# UCS.net
KiCad netlist of a schematic drawn in EAGLE
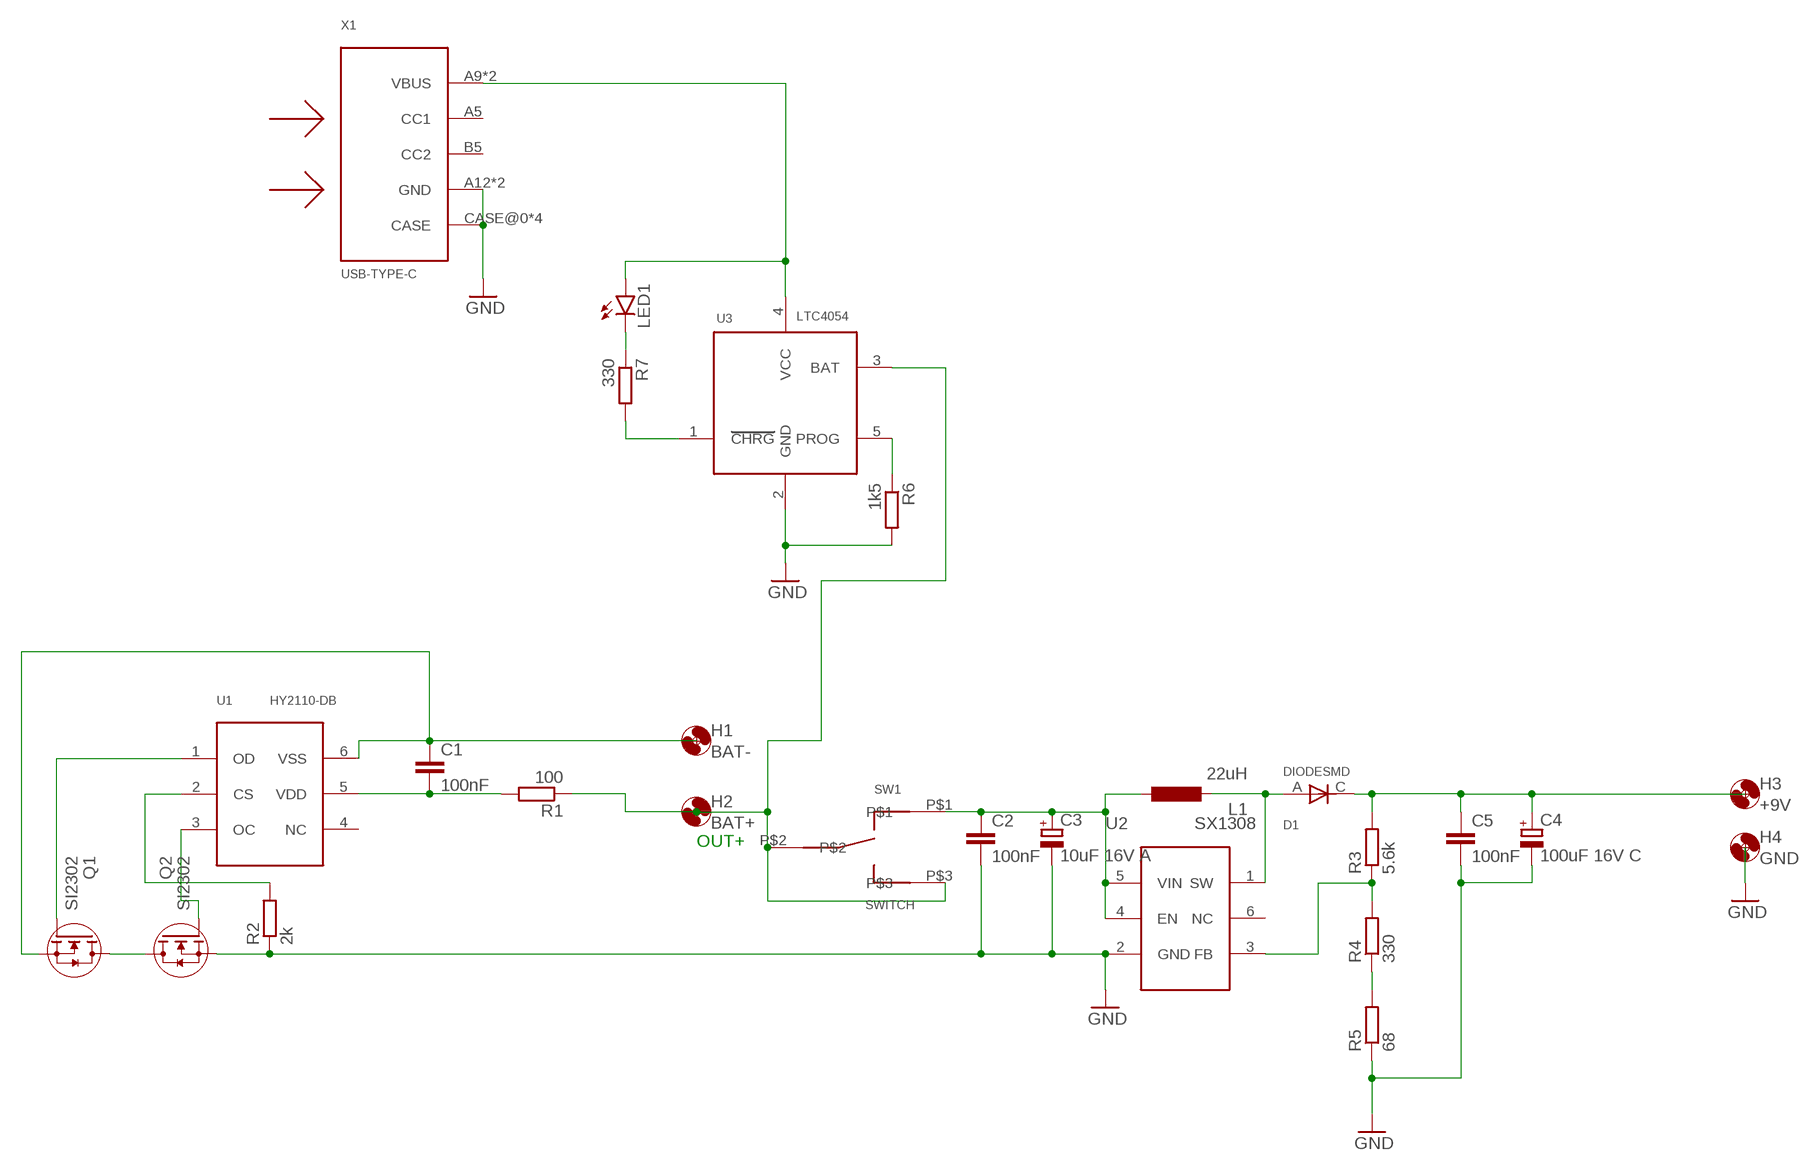
[diagram p0: schematic, sheet 1]

(export (version "E")
  (design (tool "Eeschema 10.0.6"))
  (components
    (comp (ref "C1")
      (value "100nF")
      (footprint "eagle-import:C0805")
      (libsource (lib "eagle-import") (part "C-EUC0805"))
    )
    (comp (ref "C2")
      (value "100nF")
      (footprint "eagle-import:C0805")
      (libsource (lib "eagle-import") (part "C-EUC0805"))
    )
    (comp (ref "C3")
      (value "10uF 16V A")
      (footprint "eagle-import:SMC_A")
      (libsource (lib "eagle-import") (part "CPOL-EUSMCA"))
    )
    (comp (ref "C4")
      (value "100uF 16V C")
      (footprint "eagle-import:SMC_C")
      (libsource (lib "eagle-import") (part "CPOL-EUSMCC"))
    )
    (comp (ref "C5")
      (value "100nF")
      (footprint "eagle-import:C0805")
      (libsource (lib "eagle-import") (part "C-EUC0805"))
    )
    (comp (ref "D1")
      (value "DIODESMD")
      (footprint "eagle-import:DO214AC")
      (libsource (lib "eagle-import") (part "DIODESMD"))
    )
    (comp (ref "H1")
      (value "BAT-")
      (footprint "eagle-import:3,0")
      (libsource (lib "eagle-import") (part "MOUNT-HOLE3.0"))
    )
    (comp (ref "H2")
      (value "BAT+")
      (footprint "eagle-import:3,0")
      (libsource (lib "eagle-import") (part "MOUNT-HOLE3.0"))
    )
    (comp (ref "H3")
      (value "+9V")
      (footprint "eagle-import:3,0")
      (libsource (lib "eagle-import") (part "MOUNT-HOLE3.0"))
    )
    (comp (ref "H4")
      (value "GND")
      (footprint "eagle-import:3,0")
      (libsource (lib "eagle-import") (part "MOUNT-HOLE3.0"))
    )
    (comp (ref "L1")
      (value "22uH")
      (footprint "eagle-import:L7_7_5")
      (libsource (lib "eagle-import") (part "L-SMD-775"))
    )
    (comp (ref "LED1")
      (value "LEDCHIPLED_0603")
      (footprint "eagle-import:CHIPLED_0603")
      (libsource (lib "eagle-import") (part "LEDCHIPLED_0603"))
    )
    (comp (ref "Q1")
      (value "SI2302")
      (footprint "eagle-import:SOT-23-GSD")
      (libsource (lib "eagle-import") (part "SI2302"))
    )
    (comp (ref "Q2")
      (value "SI2302")
      (footprint "eagle-import:SOT-23-GSD")
      (libsource (lib "eagle-import") (part "SI2302"))
    )
    (comp (ref "R1")
      (value "100")
      (footprint "eagle-import:R0805")
      (libsource (lib "eagle-import") (part "R-EU_R0805"))
    )
    (comp (ref "R2")
      (value "2k")
      (footprint "eagle-import:R0805")
      (libsource (lib "eagle-import") (part "R-EU_R0805"))
    )
    (comp (ref "R3")
      (value "5.6k")
      (footprint "eagle-import:R0805")
      (libsource (lib "eagle-import") (part "R-EU_R0805"))
    )
    (comp (ref "R4")
      (value "330")
      (footprint "eagle-import:R0805")
      (libsource (lib "eagle-import") (part "R-EU_R0805"))
    )
    (comp (ref "R5")
      (value "68")
      (footprint "eagle-import:R0805")
      (libsource (lib "eagle-import") (part "R-EU_R0805"))
    )
    (comp (ref "R6")
      (value "1k5")
      (footprint "eagle-import:R0805")
      (libsource (lib "eagle-import") (part "R-EU_R0805"))
    )
    (comp (ref "R7")
      (value "330")
      (footprint "eagle-import:R0805")
      (libsource (lib "eagle-import") (part "R-EU_R0805"))
    )
    (comp (ref "SW1")
      (value "SWITCH")
      (footprint "eagle-import:SWITCH")
      (libsource (lib "eagle-import") (part "SWITCH"))
    )
    (comp (ref "U1")
      (value "HY2110-DB")
      (footprint "eagle-import:SOT-23-6")
      (libsource (lib "eagle-import") (part "HY2110-DB"))
    )
    (comp (ref "U2")
      (value "SX1308")
      (footprint "eagle-import:SOT-23-6")
      (libsource (lib "eagle-import") (part "SX1308"))
    )
    (comp (ref "U3")
      (value "LTC4054")
      (footprint "eagle-import:SOT-23-5")
      (libsource (lib "eagle-import") (part "LTC4054"))
    )
    (comp (ref "X1")
      (value "USB-TYPE-C")
      (footprint "eagle-import:USB-TYPE-C")
      (libsource (lib "eagle-import") (part "USB-TYPE-C"))
    )
  )
  (nets
    (net (code "1") (name "GND") (class "Default")
      (node (ref "C2") (pin "2") (pinfunction "2_2") (pintype "passive"))
      (node (ref "C3") (pin "-") (pinfunction "-_-") (pintype "passive"))
      (node (ref "C4") (pin "-") (pinfunction "-_-") (pintype "passive"))
      (node (ref "C5") (pin "2") (pinfunction "2_2") (pintype "passive"))
      (node (ref "H4") (pin "P$1") (pinfunction "P$1_P$1") (pintype "bidirectional"))
      (node (ref "Q2") (pin "S") (pinfunction "S_S") (pintype "passive"))
      (node (ref "R2") (pin "1") (pinfunction "1_1") (pintype "passive"))
      (node (ref "R5") (pin "1") (pinfunction "1_1") (pintype "passive"))
      (node (ref "R6") (pin "2") (pinfunction "2_2") (pintype "passive"))
      (node (ref "U2") (pin "2") (pinfunction "GND_2") (pintype "bidirectional"))
      (node (ref "U3") (pin "2") (pinfunction "GND_2") (pintype "bidirectional"))
      (node (ref "X1") (pin "A12") (pinfunction "GND_A12") (pintype "bidirectional"))
      (node (ref "X1") (pin "B12") (pinfunction "GND_B12") (pintype "bidirectional"))
      (node (ref "X1") (pin "CASE@0") (pinfunction "CASE_CASE@0") (pintype "bidirectional"))
      (node (ref "X1") (pin "CASE@1") (pinfunction "CASE_CASE@1") (pintype "bidirectional"))
      (node (ref "X1") (pin "CASE@2") (pinfunction "CASE_CASE@2") (pintype "bidirectional"))
      (node (ref "X1") (pin "CASE@3") (pinfunction "CASE_CASE@3") (pintype "bidirectional"))
    )
    (net (code "2") (name "Net-(D1-ANOD)") (class "Default")
      (node (ref "D1") (pin "A") (pinfunction "ANOD_A") (pintype "power_in"))
      (node (ref "L1") (pin "P$2") (pinfunction "2_P$2") (pintype "passive"))
      (node (ref "U2") (pin "1") (pinfunction "SW_1") (pintype "bidirectional"))
    )
    (net (code "3") (name "Net-(D1-KATOD)") (class "Default")
      (node (ref "C4") (pin "+") (pinfunction "+_+") (pintype "passive"))
      (node (ref "C5") (pin "1") (pinfunction "1_1") (pintype "passive"))
      (node (ref "D1") (pin "C") (pinfunction "KATOD_C") (pintype "power_in"))
      (node (ref "H3") (pin "P$1") (pinfunction "P$1_P$1") (pintype "bidirectional"))
      (node (ref "R3") (pin "2") (pinfunction "2_2") (pintype "passive"))
    )
    (net (code "4") (name "Net-(L1-1)") (class "Default")
      (node (ref "C2") (pin "1") (pinfunction "1_1") (pintype "passive"))
      (node (ref "C3") (pin "+") (pinfunction "+_+") (pintype "passive"))
      (node (ref "L1") (pin "P$1") (pinfunction "1_P$1") (pintype "passive"))
      (node (ref "SW1") (pin "P$1") (pinfunction "P$1_P$1") (pintype "bidirectional"))
      (node (ref "U2") (pin "4") (pinfunction "EN_4") (pintype "bidirectional"))
      (node (ref "U2") (pin "5") (pinfunction "VIN_5") (pintype "bidirectional"))
    )
    (net (code "5") (name "Net-(LED1-PadC)") (class "Default")
      (node (ref "LED1") (pin "C") (pinfunction "C_C") (pintype "passive"))
      (node (ref "R7") (pin "1") (pinfunction "1_1") (pintype "passive"))
    )
    (net (code "6") (name "Net-(Q1-PadD)") (class "Default")
      (node (ref "Q1") (pin "D") (pinfunction "D_D") (pintype "passive"))
      (node (ref "Q2") (pin "D") (pinfunction "D_D") (pintype "passive"))
    )
    (net (code "7") (name "Net-(R4-Pad1)") (class "Default")
      (node (ref "R4") (pin "1") (pinfunction "1_1") (pintype "passive"))
      (node (ref "R5") (pin "2") (pinfunction "2_2") (pintype "passive"))
    )
    (net (code "8") (name "Net-(U1-CS)") (class "Default")
      (node (ref "R2") (pin "2") (pinfunction "2_2") (pintype "passive"))
      (node (ref "U1") (pin "2") (pinfunction "CS_2") (pintype "bidirectional"))
    )
    (net (code "9") (name "Net-(U1-OC)") (class "Default")
      (node (ref "Q2") (pin "G") (pinfunction "G_G") (pintype "passive"))
      (node (ref "U1") (pin "3") (pinfunction "OC_3") (pintype "bidirectional"))
    )
    (net (code "10") (name "Net-(U1-OD)") (class "Default")
      (node (ref "Q1") (pin "G") (pinfunction "G_G") (pintype "passive"))
      (node (ref "U1") (pin "1") (pinfunction "OD_1") (pintype "bidirectional"))
    )
    (net (code "11") (name "Net-(U1-VDD)") (class "Default")
      (node (ref "C1") (pin "2") (pinfunction "2_2") (pintype "passive"))
      (node (ref "R1") (pin "2") (pinfunction "2_2") (pintype "passive"))
      (node (ref "U1") (pin "5") (pinfunction "VDD_5") (pintype "bidirectional"))
    )
    (net (code "12") (name "Net-(U1-VSS)") (class "Default")
      (node (ref "C1") (pin "1") (pinfunction "1_1") (pintype "passive"))
      (node (ref "H1") (pin "P$1") (pinfunction "P$1_P$1") (pintype "bidirectional"))
      (node (ref "Q1") (pin "S") (pinfunction "S_S") (pintype "passive"))
      (node (ref "U1") (pin "6") (pinfunction "VSS_6") (pintype "bidirectional"))
    )
    (net (code "13") (name "Net-(U2-FB)") (class "Default")
      (node (ref "R3") (pin "1") (pinfunction "1_1") (pintype "passive"))
      (node (ref "R4") (pin "2") (pinfunction "2_2") (pintype "passive"))
      (node (ref "U2") (pin "3") (pinfunction "FB_3") (pintype "bidirectional"))
    )
    (net (code "14") (name "Net-(U3-BAT)") (class "Default")
      (node (ref "H2") (pin "P$1") (pinfunction "P$1_P$1") (pintype "bidirectional"))
      (node (ref "R1") (pin "1") (pinfunction "1_1") (pintype "passive"))
      (node (ref "SW1") (pin "P$2") (pinfunction "P$2_P$2") (pintype "bidirectional"))
      (node (ref "SW1") (pin "P$3") (pinfunction "P$3_P$3") (pintype "bidirectional"))
      (node (ref "U3") (pin "3") (pinfunction "BAT_3") (pintype "bidirectional"))
    )
    (net (code "15") (name "Net-(U3-CHRG)") (class "Default")
      (node (ref "R7") (pin "2") (pinfunction "2_2") (pintype "passive"))
      (node (ref "U3") (pin "1") (pinfunction "CHRG_1") (pintype "bidirectional"))
    )
    (net (code "16") (name "Net-(U3-PROG)") (class "Default")
      (node (ref "R6") (pin "1") (pinfunction "1_1") (pintype "passive"))
      (node (ref "U3") (pin "5") (pinfunction "PROG_5") (pintype "bidirectional"))
    )
    (net (code "17") (name "Net-(U3-VCC)") (class "Default")
      (node (ref "LED1") (pin "A") (pinfunction "A_A") (pintype "passive"))
      (node (ref "U3") (pin "4") (pinfunction "VCC_4") (pintype "bidirectional"))
      (node (ref "X1") (pin "A9") (pinfunction "VBUS_A9") (pintype "bidirectional"))
      (node (ref "X1") (pin "B9") (pinfunction "VBUS_B9") (pintype "bidirectional"))
    )
    (net (code "18") (name "unconnected-(U1-NC-Pad4)") (class "Default")
      (node (ref "U1") (pin "4") (pinfunction "NC_4") (pintype "bidirectional"))
    )
    (net (code "19") (name "unconnected-(U2-NC-Pad6)") (class "Default")
      (node (ref "U2") (pin "6") (pinfunction "NC_6") (pintype "bidirectional"))
    )
    (net (code "20") (name "unconnected-(X1-CC1-PadA5)") (class "Default")
      (node (ref "X1") (pin "A5") (pinfunction "CC1_A5") (pintype "bidirectional"))
    )
    (net (code "21") (name "unconnected-(X1-CC2-PadB5)") (class "Default")
      (node (ref "X1") (pin "B5") (pinfunction "CC2_B5") (pintype "bidirectional"))
    )
  )
)
